# design.net
KiCad netlist of a schematic drawn in Altium Designer
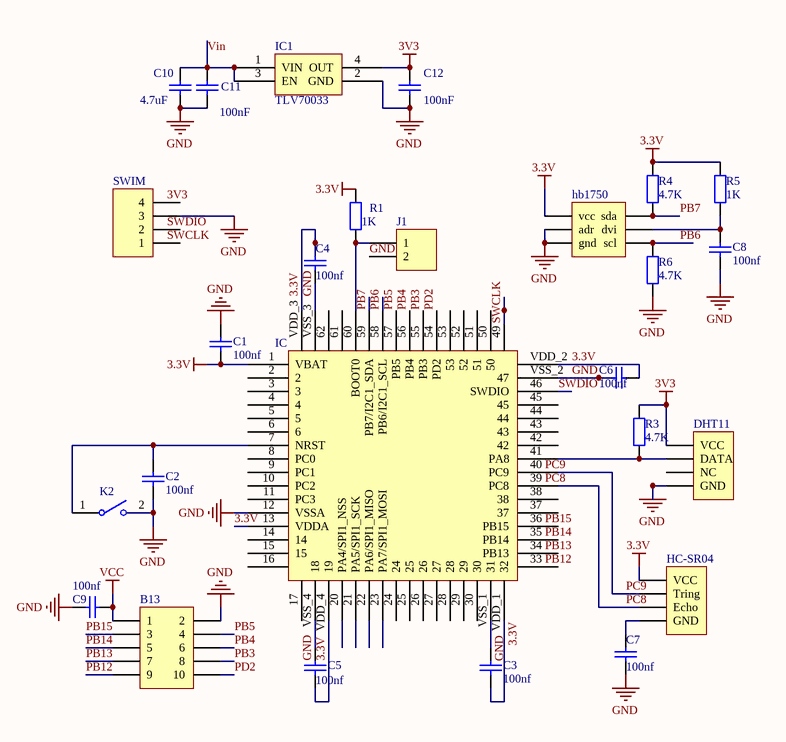
[diagram p0: 原理图.SchDoc]

(export (version "E")
  (design (tool "Eeschema 10.0.6"))
  (components
    (comp (ref "B13")
      (value "Header 5X2")
      (footprint "HDR2X5")
      (description "Header, 5-Pin, Dual row")
      (fields (field (name "PUBLISHER") "Altium Limited"))
      (libsource (lib "Miscellaneous Connectors") (part "Header 5X2"))
    )
    (comp (ref "C1")
      (value "100nf")
      (footprint "0603C")
      (description "Capacitor")
      (fields (field (name "Comment") "Cap") (field (name "PUBLISHER") "Altium Limited"))
      (libsource (lib "Miscellaneous Devices") (part "Cap"))
    )
    (comp (ref "C2")
      (value "100nf")
      (footprint "0603C")
      (description "Capacitor")
      (fields (field (name "Comment") "Cap") (field (name "PUBLISHER") "Altium Limited"))
      (libsource (lib "Miscellaneous Devices") (part "Cap"))
    )
    (comp (ref "C3")
      (value "100nf")
      (footprint "0603C")
      (description "Capacitor")
      (fields (field (name "Comment") "Cap") (field (name "PUBLISHER") "Altium Limited"))
      (libsource (lib "Miscellaneous Devices") (part "Cap"))
    )
    (comp (ref "C4")
      (value "100nf")
      (footprint "0603C")
      (description "Capacitor")
      (fields (field (name "Comment") "Cap") (field (name "PUBLISHER") "Altium Limited"))
      (libsource (lib "Miscellaneous Devices") (part "Cap"))
    )
    (comp (ref "C5")
      (value "100nf")
      (footprint "0603C")
      (description "Capacitor")
      (fields (field (name "Comment") "Cap") (field (name "PUBLISHER") "Altium Limited"))
      (libsource (lib "Miscellaneous Devices") (part "Cap"))
    )
    (comp (ref "C6")
      (value "100nf")
      (footprint "0603C")
      (description "Capacitor")
      (fields (field (name "Comment") "Cap") (field (name "PUBLISHER") "Altium Limited"))
      (libsource (lib "Miscellaneous Devices") (part "Cap"))
    )
    (comp (ref "C7")
      (value "100nf")
      (footprint "0603C")
      (description "Capacitor")
      (fields (field (name "Comment") "Cap") (field (name "PUBLISHER") "Altium Limited"))
      (libsource (lib "Miscellaneous Devices") (part "Cap"))
    )
    (comp (ref "C8")
      (value "100nf")
      (footprint "0603C")
      (description "Capacitor")
      (fields (field (name "Comment") "Cap") (field (name "PUBLISHER") "Altium Limited"))
      (libsource (lib "Miscellaneous Devices") (part "Cap"))
    )
    (comp (ref "C9")
      (value "100nf")
      (footprint "0603C")
      (description "Capacitor")
      (fields (field (name "Comment") "Cap") (field (name "PUBLISHER") "Altium Limited"))
      (libsource (lib "Miscellaneous Devices") (part "Cap"))
    )
    (comp (ref "C10")
      (value "4.7uF")
      (footprint "0603C")
      (description "Capacitor")
      (fields (field (name "Comment") "Cap") (field (name "PUBLISHER") "Altium Limited"))
      (libsource (lib "Miscellaneous Devices") (part "Cap"))
    )
    (comp (ref "C11")
      (value "100nF")
      (footprint "0603C")
      (description "Capacitor")
      (fields (field (name "Comment") "Cap") (field (name "PUBLISHER") "Altium Limited"))
      (libsource (lib "Miscellaneous Devices") (part "Cap"))
    )
    (comp (ref "C12")
      (value "100nF")
      (footprint "0603C")
      (description "Capacitor")
      (fields (field (name "Comment") "Cap") (field (name "PUBLISHER") "Altium Limited"))
      (libsource (lib "Miscellaneous Devices") (part "Cap"))
    )
    (comp (ref "DHT11")
      (value "Header 4")
      (footprint "HDR1X4")
      (description "Header, 4-Pin")
      (fields (field (name "PUBLISHER") "Altium Limited"))
      (libsource (lib "") (part "Header 4_1"))
    )
    (comp (ref "hb1750")
      (value "~")
      (footprint "HDR2X3")
      (description "Header, 3-Pin, Dual row")
      (fields (field (name "PUBLISHER") "Altium Limited"))
      (libsource (lib "Miscellaneous Connectors") (part "Header 3X2"))
    )
    (comp (ref "HC-SR04")
      (value "Header 4")
      (footprint "HDR1X4")
      (description "Header, 4-Pin")
      (fields (field (name "PUBLISHER") "Altium Limited"))
      (libsource (lib "Miscellaneous Connectors") (part "Header 4"))
    )
    (comp (ref "IC") (value "~") (libsource (lib "STM32RC") (part "Component_1")))
    (comp (ref "IC1")
      (value "TLV70033")
      (footprint "TLV71330:PCBComponent_1")
      (libsource (lib "TLV71330") (part "Component_1"))
    )
    (comp (ref "J1")
      (value "~")
      (footprint "HDR1X2")
      (description "Header, 2-Pin")
      (fields (field (name "PUBLISHER") "Altium Limited"))
      (libsource (lib "Miscellaneous Connectors") (part "Header 2"))
    )
    (comp (ref "K2")
      (value "SW-SPST")
      (footprint "SOP4")
      (description "Single-Pole, Single-Throw Switch")
      (fields (field (name "PUBLISHER") "Altium Limited"))
      (libsource (lib "Miscellaneous Devices") (part "SW-SPST"))
    )
    (comp (ref "R1")
      (value "1K")
      (footprint "0603C")
      (description "Resistor")
      (fields (field (name "Comment") "Res2") (field (name "PUBLISHER") "Altium Limited"))
      (libsource (lib "Miscellaneous Devices") (part "Res2"))
    )
    (comp (ref "R3")
      (value "4.7K")
      (footprint "0603C")
      (description "Resistor")
      (fields (field (name "Comment") "Res2") (field (name "PUBLISHER") "Altium Limited"))
      (libsource (lib "Miscellaneous Devices") (part "Res2"))
    )
    (comp (ref "R4")
      (value "4.7K")
      (footprint "0603C")
      (description "Resistor")
      (fields (field (name "Comment") "Res2") (field (name "PUBLISHER") "Altium Limited"))
      (libsource (lib "Miscellaneous Devices") (part "Res2"))
    )
    (comp (ref "R5")
      (value "1K")
      (footprint "0603C")
      (description "Resistor")
      (fields (field (name "Comment") "Res2") (field (name "PUBLISHER") "Altium Limited"))
      (libsource (lib "Miscellaneous Devices") (part "Res2"))
    )
    (comp (ref "R6")
      (value "4.7K")
      (footprint "0603C")
      (description "Resistor")
      (fields (field (name "Comment") "Res2") (field (name "PUBLISHER") "Altium Limited"))
      (libsource (lib "Miscellaneous Devices") (part "Res2"))
    )
    (comp (ref "SWIM")
      (value "Header 4")
      (footprint "HDR1X4")
      (description "Header, 4-Pin")
      (fields (field (name "PUBLISHER") "Altium Limited"))
      (libsource (lib "") (part "Header 4_2"))
    )
  )
  (nets
    (net (code "1") (name "/PB3") (class "Default")
      (node (ref "B13") (pin "8") (pinfunction "8_8") (pintype "passive"))
      (node (ref "IC") (pin "55") (pinfunction "PB3_55") (pintype "passive"))
    )
    (net (code "2") (name "/PB4") (class "Default")
      (node (ref "B13") (pin "6") (pinfunction "6_6") (pintype "passive"))
      (node (ref "IC") (pin "56") (pinfunction "PB4_56") (pintype "passive"))
    )
    (net (code "3") (name "/PB5") (class "Default")
      (node (ref "B13") (pin "4") (pinfunction "4_4") (pintype "passive"))
      (node (ref "IC") (pin "57") (pinfunction "PB5_57") (pintype "passive"))
    )
    (net (code "4") (name "/PB6") (class "Default")
      (node (ref "IC") (pin "58") (pinfunction "PB6/I2C1_SCL_58") (pintype "passive"))
      (node (ref "R6") (pin "1") (pinfunction "1_1") (pintype "passive"))
      (node (ref "hb1750") (pin "6") (pinfunction "scl_6") (pintype "passive"))
    )
    (net (code "5") (name "/PB7") (class "Default")
      (node (ref "IC") (pin "59") (pinfunction "PB7/I2C1_SDA_59") (pintype "passive"))
      (node (ref "R4") (pin "2") (pinfunction "2_2") (pintype "passive"))
      (node (ref "hb1750") (pin "2") (pinfunction "sda_2") (pintype "passive"))
    )
    (net (code "6") (name "/PB12") (class "Default")
      (node (ref "B13") (pin "9") (pinfunction "9_9") (pintype "passive"))
    )
    (net (code "7") (name "/PB13") (class "Default")
      (node (ref "B13") (pin "7") (pinfunction "7_7") (pintype "passive"))
    )
    (net (code "8") (name "/PB14") (class "Default")
      (node (ref "B13") (pin "5") (pinfunction "5_5") (pintype "passive"))
    )
    (net (code "9") (name "/PB15") (class "Default")
      (node (ref "B13") (pin "3") (pinfunction "3_3") (pintype "passive"))
    )
    (net (code "10") (name "/PC8") (class "Default")
      (node (ref "HC-SR04") (pin "3") (pinfunction "Echo_3") (pintype "passive"))
      (node (ref "IC") (pin "39") (pinfunction "PC8_39") (pintype "passive"))
    )
    (net (code "11") (name "/PC9") (class "Default")
      (node (ref "HC-SR04") (pin "2") (pinfunction "Tring_2") (pintype "passive"))
      (node (ref "IC") (pin "40") (pinfunction "PC9_40") (pintype "passive"))
    )
    (net (code "12") (name "/PD2") (class "Default")
      (node (ref "B13") (pin "10") (pinfunction "10_10") (pintype "passive"))
      (node (ref "IC") (pin "54") (pinfunction "PD2_54") (pintype "passive"))
    )
    (net (code "13") (name "/SWCLK") (class "Default") (node (ref "IC") (pin "49") (pintype "passive")))
    (net (code "14") (name "/SWDIO") (class "Default")
      (node (ref "IC") (pin "46") (pinfunction "SWDIO_46") (pintype "passive"))
    )
    (net (code "15") (name "/Vin") (class "Default")
      (node (ref "C10") (pin "2") (pinfunction "2_2") (pintype "passive"))
      (node (ref "C11") (pin "2") (pinfunction "2_2") (pintype "passive"))
      (node (ref "IC1") (pin "1") (pinfunction "VIN_1") (pintype "passive"))
      (node (ref "IC1") (pin "3") (pinfunction "EN_3") (pintype "passive"))
    )
    (net (code "16") (name "3.3V") (class "Default")
      (node (ref "C1") (pin "2") (pinfunction "2_2") (pintype "passive"))
      (node (ref "C3") (pin "1") (pinfunction "1_1") (pintype "passive"))
      (node (ref "C4") (pin "2") (pinfunction "2_2") (pintype "passive"))
      (node (ref "C5") (pin "1") (pinfunction "1_1") (pintype "passive"))
      (node (ref "C6") (pin "2") (pinfunction "2_2") (pintype "passive"))
      (node (ref "HC-SR04") (pin "1") (pinfunction "VCC_1") (pintype "passive"))
      (node (ref "IC") (pin "1") (pinfunction "VBAT_1") (pintype "passive"))
      (node (ref "IC") (pin "13") (pinfunction "VDDA_13") (pintype "passive"))
      (node (ref "IC") (pin "VDD_1") (pinfunction "32_VDD_1") (pintype "passive"))
      (node (ref "IC") (pin "VDD_2") (pintype "passive"))
      (node (ref "IC") (pin "VDD_3") (pintype "passive"))
      (node (ref "IC") (pin "VDD_4") (pinfunction "19_VDD_4") (pintype "passive"))
      (node (ref "R1") (pin "1") (pinfunction "1_1") (pintype "passive"))
      (node (ref "R4") (pin "1") (pinfunction "1_1") (pintype "passive"))
      (node (ref "R5") (pin "1") (pinfunction "1_1") (pintype "passive"))
      (node (ref "hb1750") (pin "1") (pinfunction "vcc_1") (pintype "passive"))
    )
    (net (code "17") (name "3V3") (class "Default")
      (node (ref "C12") (pin "2") (pinfunction "2_2") (pintype "passive"))
      (node (ref "DHT11") (pin "1") (pinfunction "VCC_1") (pintype "passive"))
      (node (ref "IC1") (pin "4") (pinfunction "OUT_4") (pintype "passive"))
      (node (ref "R3") (pin "1") (pinfunction "1_1") (pintype "passive"))
    )
    (net (code "18") (name "GND") (class "Default")
      (node (ref "B13") (pin "2") (pinfunction "2_2") (pintype "passive"))
      (node (ref "C1") (pin "1") (pinfunction "1_1") (pintype "passive"))
      (node (ref "C10") (pin "1") (pinfunction "1_1") (pintype "passive"))
      (node (ref "C11") (pin "1") (pinfunction "1_1") (pintype "passive"))
      (node (ref "C12") (pin "1") (pinfunction "1_1") (pintype "passive"))
      (node (ref "C2") (pin "2") (pinfunction "2_2") (pintype "passive"))
      (node (ref "C3") (pin "2") (pinfunction "2_2") (pintype "passive"))
      (node (ref "C4") (pin "1") (pinfunction "1_1") (pintype "passive"))
      (node (ref "C6") (pin "1") (pinfunction "1_1") (pintype "passive"))
      (node (ref "C7") (pin "1") (pinfunction "1_1") (pintype "passive"))
      (node (ref "C8") (pin "1") (pinfunction "1_1") (pintype "passive"))
      (node (ref "C9") (pin "1") (pinfunction "1_1") (pintype "passive"))
      (node (ref "DHT11") (pin "4") (pinfunction "GND_4") (pintype "passive"))
      (node (ref "IC") (pin "12") (pinfunction "VSSA_12") (pintype "passive"))
      (node (ref "IC") (pin "VSS_1") (pinfunction "31_VSS_1") (pintype "passive"))
      (node (ref "IC") (pin "VSS_2") (pinfunction "47_VSS_2") (pintype "passive"))
      (node (ref "IC") (pin "VSS_3") (pintype "passive"))
      (node (ref "IC1") (pin "2") (pinfunction "GND_2") (pintype "passive"))
      (node (ref "J1") (pin "2") (pinfunction "2_2") (pintype "passive"))
      (node (ref "K2") (pin "2") (pinfunction "NO_2") (pintype "passive"))
      (node (ref "R6") (pin "2") (pinfunction "2_2") (pintype "passive"))
      (node (ref "SWIM") (pin "3") (pinfunction "3_3") (pintype "passive"))
      (node (ref "hb1750") (pin "3") (pinfunction "adr_3") (pintype "passive"))
      (node (ref "hb1750") (pin "5") (pinfunction "gnd_5") (pintype "passive"))
    )
    (net (code "19") (name "Net-(DHT11-DATA)") (class "Default")
      (node (ref "DHT11") (pin "2") (pinfunction "DATA_2") (pintype "passive"))
      (node (ref "IC") (pin "41") (pinfunction "PA8_41") (pintype "passive"))
      (node (ref "R3") (pin "2") (pinfunction "2_2") (pintype "passive"))
    )
    (net (code "20") (name "Net-(HC-SR04-GND)") (class "Default")
      (node (ref "C7") (pin "2") (pinfunction "2_2") (pintype "passive"))
      (node (ref "HC-SR04") (pin "4") (pinfunction "GND_4") (pintype "passive"))
    )
    (net (code "21") (name "Net-(IC-18)") (class "Default")
      (node (ref "C5") (pin "2") (pinfunction "2_2") (pintype "passive"))
      (node (ref "IC") (pin "VSS_4") (pinfunction "18_VSS_4") (pintype "passive"))
    )
    (net (code "22") (name "Net-(IC-BOOT0)") (class "Default")
      (node (ref "IC") (pin "60") (pinfunction "BOOT0_60") (pintype "passive"))
      (node (ref "J1") (pin "1") (pinfunction "1_1") (pintype "passive"))
      (node (ref "R1") (pin "2") (pinfunction "2_2") (pintype "passive"))
    )
    (net (code "23") (name "Net-(IC-NRST)") (class "Default")
      (node (ref "C2") (pin "1") (pinfunction "1_1") (pintype "passive"))
      (node (ref "IC") (pin "7") (pinfunction "NRST_7") (pintype "passive"))
      (node (ref "K2") (pin "1") (pinfunction "COMMON_1") (pintype "passive"))
    )
    (net (code "24") (name "Net-(hb1750-dvi)") (class "Default")
      (node (ref "C8") (pin "2") (pinfunction "2_2") (pintype "passive"))
      (node (ref "R5") (pin "2") (pinfunction "2_2") (pintype "passive"))
      (node (ref "hb1750") (pin "4") (pinfunction "dvi_4") (pintype "passive"))
    )
    (net (code "25") (name "VCC") (class "Default")
      (node (ref "B13") (pin "1") (pinfunction "1_1") (pintype "passive"))
      (node (ref "C9") (pin "2") (pinfunction "2_2") (pintype "passive"))
    )
    (net (code "26") (name "unconnected-(DHT11-NC-Pad3)") (class "Default")
      (node (ref "DHT11") (pin "3") (pinfunction "NC_3") (pintype "passive"))
    )
    (net (code "27") (name "unconnected-(IC-PA4{slash}SPI1_NSS-Pad20)") (class "Default")
      (node (ref "IC") (pin "20") (pinfunction "PA4/SPI1_NSS_20") (pintype "passive"))
    )
    (net (code "28") (name "unconnected-(IC-PA5{slash}SPI1_SCK-Pad21)") (class "Default")
      (node (ref "IC") (pin "21") (pinfunction "PA5/SPI1_SCK_21") (pintype "passive"))
    )
    (net (code "29") (name "unconnected-(IC-PA6{slash}SPI1_MISO-Pad22)") (class "Default")
      (node (ref "IC") (pin "22") (pinfunction "PA6/SPI1_MISO_22") (pintype "passive"))
    )
    (net (code "30") (name "unconnected-(IC-PA7{slash}SPI1_MOSI-Pad23)") (class "Default")
      (node (ref "IC") (pin "23") (pinfunction "PA7/SPI1_MOSI_23") (pintype "passive"))
    )
    (net (code "31") (name "unconnected-(IC-PB13-Pad34)") (class "Default")
      (node (ref "IC") (pin "34") (pinfunction "PB13_34") (pintype "passive"))
    )
    (net (code "32") (name "unconnected-(IC-PB14-Pad35)") (class "Default")
      (node (ref "IC") (pin "35") (pinfunction "PB14_35") (pintype "passive"))
    )
    (net (code "33") (name "unconnected-(IC-PB15-Pad36)") (class "Default")
      (node (ref "IC") (pin "36") (pinfunction "PB15_36") (pintype "passive"))
    )
    (net (code "34") (name "unconnected-(IC-PC0-Pad8)") (class "Default")
      (node (ref "IC") (pin "8") (pinfunction "PC0_8") (pintype "passive"))
    )
    (net (code "35") (name "unconnected-(IC-PC1-Pad9)") (class "Default")
      (node (ref "IC") (pin "9") (pinfunction "PC1_9") (pintype "passive"))
    )
    (net (code "36") (name "unconnected-(IC-PC2-Pad10)") (class "Default")
      (node (ref "IC") (pin "10") (pinfunction "PC2_10") (pintype "passive"))
    )
    (net (code "37") (name "unconnected-(IC-PC3-Pad11)") (class "Default")
      (node (ref "IC") (pin "11") (pinfunction "PC3_11") (pintype "passive"))
    )
    (net (code "38") (name "unconnected-(IC-Pad2)") (class "Default")
      (node (ref "IC") (pin "2") (pinfunction "2_2") (pintype "passive"))
    )
    (net (code "39") (name "unconnected-(IC-Pad3)") (class "Default")
      (node (ref "IC") (pin "3") (pinfunction "3_3") (pintype "passive"))
    )
    (net (code "40") (name "unconnected-(IC-Pad4)") (class "Default")
      (node (ref "IC") (pin "4") (pinfunction "4_4") (pintype "passive"))
    )
    (net (code "41") (name "unconnected-(IC-Pad5)") (class "Default")
      (node (ref "IC") (pin "5") (pinfunction "5_5") (pintype "passive"))
    )
    (net (code "42") (name "unconnected-(IC-Pad6)") (class "Default")
      (node (ref "IC") (pin "6") (pinfunction "6_6") (pintype "passive"))
    )
    (net (code "43") (name "unconnected-(IC-Pad14)") (class "Default")
      (node (ref "IC") (pin "14") (pinfunction "14_14") (pintype "passive"))
    )
    (net (code "44") (name "unconnected-(IC-Pad15)") (class "Default")
      (node (ref "IC") (pin "15") (pinfunction "15_15") (pintype "passive"))
    )
    (net (code "45") (name "unconnected-(IC-Pad16)") (class "Default")
      (node (ref "IC") (pin "16") (pintype "passive"))
    )
    (net (code "46") (name "unconnected-(IC-Pad17)") (class "Default")
      (node (ref "IC") (pin "17") (pintype "passive"))
    )
    (net (code "47") (name "unconnected-(IC-Pad24)") (class "Default")
      (node (ref "IC") (pin "24") (pinfunction "24_24") (pintype "passive"))
    )
    (net (code "48") (name "unconnected-(IC-Pad25)") (class "Default")
      (node (ref "IC") (pin "25") (pinfunction "25_25") (pintype "passive"))
    )
    (net (code "49") (name "unconnected-(IC-Pad26)") (class "Default")
      (node (ref "IC") (pin "26") (pinfunction "26_26") (pintype "passive"))
    )
    (net (code "50") (name "unconnected-(IC-Pad27)") (class "Default")
      (node (ref "IC") (pin "27") (pinfunction "27_27") (pintype "passive"))
    )
    (net (code "51") (name "unconnected-(IC-Pad28)") (class "Default")
      (node (ref "IC") (pin "28") (pinfunction "28_28") (pintype "passive"))
    )
    (net (code "52") (name "unconnected-(IC-Pad29)") (class "Default")
      (node (ref "IC") (pin "29") (pinfunction "29_29") (pintype "passive"))
    )
    (net (code "53") (name "unconnected-(IC-Pad30)") (class "Default")
      (node (ref "IC") (pin "30") (pinfunction "30_30") (pintype "passive"))
    )
    (net (code "54") (name "unconnected-(IC-Pad33)") (class "Default")
      (node (ref "IC") (pin "33") (pintype "passive"))
    )
    (net (code "55") (name "unconnected-(IC-Pad37)") (class "Default")
      (node (ref "IC") (pin "37") (pinfunction "37_37") (pintype "passive"))
    )
    (net (code "56") (name "unconnected-(IC-Pad38)") (class "Default")
      (node (ref "IC") (pin "38") (pinfunction "38_38") (pintype "passive"))
    )
    (net (code "57") (name "unconnected-(IC-Pad42)") (class "Default")
      (node (ref "IC") (pin "42") (pinfunction "42_42") (pintype "passive"))
    )
    (net (code "58") (name "unconnected-(IC-Pad43)") (class "Default")
      (node (ref "IC") (pin "43") (pinfunction "43_43") (pintype "passive"))
    )
    (net (code "59") (name "unconnected-(IC-Pad44)") (class "Default")
      (node (ref "IC") (pin "44") (pinfunction "44_44") (pintype "passive"))
    )
    (net (code "60") (name "unconnected-(IC-Pad45)") (class "Default")
      (node (ref "IC") (pin "45") (pinfunction "45_45") (pintype "passive"))
    )
    (net (code "61") (name "unconnected-(IC-Pad50)") (class "Default")
      (node (ref "IC") (pin "50") (pinfunction "50_50") (pintype "passive"))
    )
    (net (code "62") (name "unconnected-(IC-Pad51)") (class "Default")
      (node (ref "IC") (pin "51") (pinfunction "51_51") (pintype "passive"))
    )
    (net (code "63") (name "unconnected-(IC-Pad52)") (class "Default")
      (node (ref "IC") (pin "52") (pinfunction "52_52") (pintype "passive"))
    )
    (net (code "64") (name "unconnected-(IC-Pad53)") (class "Default")
      (node (ref "IC") (pin "53") (pinfunction "53_53") (pintype "passive"))
    )
    (net (code "65") (name "unconnected-(IC-Pad61)") (class "Default")
      (node (ref "IC") (pin "61") (pintype "passive"))
    )
    (net (code "66") (name "unconnected-(IC-Pad62)") (class "Default")
      (node (ref "IC") (pin "62") (pintype "passive"))
    )
    (net (code "67") (name "unconnected-(SWIM-Pad1)") (class "Default")
      (node (ref "SWIM") (pin "1") (pinfunction "1_1") (pintype "passive"))
    )
    (net (code "68") (name "unconnected-(SWIM-Pad2)") (class "Default")
      (node (ref "SWIM") (pin "2") (pinfunction "2_2") (pintype "passive"))
    )
    (net (code "69") (name "unconnected-(SWIM-Pad4)") (class "Default")
      (node (ref "SWIM") (pin "4") (pinfunction "4_4") (pintype "passive"))
    )
  )
)
